# spinner.net
KiCad netlist of a schematic drawn in EAGLE
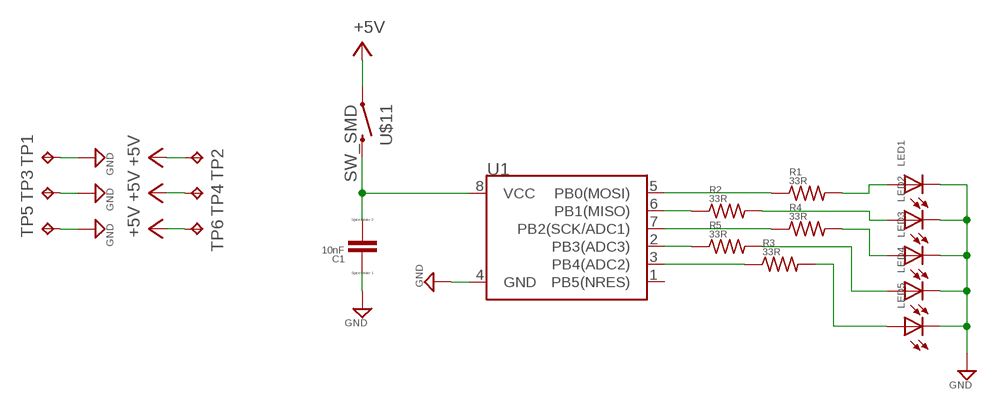
[diagram p0: schematic, sheet 1]

(export (version "E")
  (design (tool "Eeschema 10.0.6"))
  (components
    (comp (ref "C1")
      (value "10nF")
      (footprint "eagle-import:0603")
      (libsource (lib "eagle-import") (part "CAPACITOR-CERAMICOB"))
    )
    (comp (ref "LED1")
      (value "LEDC")
      (footprint "eagle-import:0603LED")
      (libsource (lib "eagle-import") (part "LEDC"))
    )
    (comp (ref "LED2")
      (value "LEDC")
      (footprint "eagle-import:0603LED")
      (libsource (lib "eagle-import") (part "LEDC"))
    )
    (comp (ref "LED3")
      (value "LEDC")
      (footprint "eagle-import:0603LED")
      (libsource (lib "eagle-import") (part "LEDC"))
    )
    (comp (ref "LED4")
      (value "LEDC")
      (footprint "eagle-import:0603LED")
      (libsource (lib "eagle-import") (part "LEDC"))
    )
    (comp (ref "LED5")
      (value "LEDC")
      (footprint "eagle-import:0603LED")
      (libsource (lib "eagle-import") (part "LEDC"))
    )
    (comp (ref "R1")
      (value "33R")
      (footprint "eagle-import:0603")
      (libsource (lib "eagle-import") (part "RESISTORB"))
    )
    (comp (ref "R2")
      (value "33R")
      (footprint "eagle-import:0603")
      (libsource (lib "eagle-import") (part "RESISTORB"))
    )
    (comp (ref "R3")
      (value "33R")
      (footprint "eagle-import:0603")
      (libsource (lib "eagle-import") (part "RESISTORB"))
    )
    (comp (ref "R4")
      (value "33R")
      (footprint "eagle-import:0603")
      (libsource (lib "eagle-import") (part "RESISTORB"))
    )
    (comp (ref "R5")
      (value "33R")
      (footprint "eagle-import:0603")
      (libsource (lib "eagle-import") (part "RESISTORB"))
    )
    (comp (ref "TP1")
      (value "TPB1,27")
      (footprint "eagle-import:B1,27")
      (libsource (lib "eagle-import") (part "TPB1,27"))
    )
    (comp (ref "TP2")
      (value "TPB1,27")
      (footprint "eagle-import:B1,27")
      (libsource (lib "eagle-import") (part "TPB1,27"))
    )
    (comp (ref "TP3")
      (value "TPB1,27")
      (footprint "eagle-import:B1,27")
      (libsource (lib "eagle-import") (part "TPB1,27"))
    )
    (comp (ref "TP4")
      (value "TPB1,27")
      (footprint "eagle-import:B1,27")
      (libsource (lib "eagle-import") (part "TPB1,27"))
    )
    (comp (ref "TP5")
      (value "TPB1,27")
      (footprint "eagle-import:B1,27")
      (libsource (lib "eagle-import") (part "TPB1,27"))
    )
    (comp (ref "TP6")
      (value "TPB1,27")
      (footprint "eagle-import:B1,27")
      (libsource (lib "eagle-import") (part "TPB1,27"))
    )
    (comp (ref "U$11")
      (value "SW_SMD")
      (footprint "eagle-import:SW_SMD")
      (libsource (lib "eagle-import") (part "SW_SMD"))
    )
    (comp (ref "U1")
      (value "Tiny85-20-SMT")
      (footprint "eagle-import:SO08-EIAJ")
      (libsource (lib "eagle-import") (part "ATTINY45"))
    )
  )
  (nets
    (net (code "1") (name "+5V") (class "Default")
      (node (ref "TP2") (pin "TP") (pinfunction "TP_TP") (pintype "input"))
      (node (ref "TP4") (pin "TP") (pinfunction "TP_TP") (pintype "input"))
      (node (ref "TP6") (pin "TP") (pinfunction "TP_TP") (pintype "input"))
      (node (ref "U$11") (pin "1") (pinfunction "1_1") (pintype "passive"))
    )
    (net (code "2") (name "GND") (class "Default")
      (node (ref "C1") (pin "1") (pinfunction "1_1") (pintype "passive"))
      (node (ref "LED1") (pin "K") (pinfunction "C_K") (pintype "passive"))
      (node (ref "LED2") (pin "K") (pinfunction "C_K") (pintype "passive"))
      (node (ref "LED3") (pin "K") (pinfunction "C_K") (pintype "passive"))
      (node (ref "LED4") (pin "K") (pinfunction "C_K") (pintype "passive"))
      (node (ref "LED5") (pin "K") (pinfunction "C_K") (pintype "passive"))
      (node (ref "TP1") (pin "TP") (pinfunction "TP_TP") (pintype "input"))
      (node (ref "TP3") (pin "TP") (pinfunction "TP_TP") (pintype "input"))
      (node (ref "TP5") (pin "TP") (pinfunction "TP_TP") (pintype "input"))
      (node (ref "U1") (pin "4") (pinfunction "GND_4") (pintype "bidirectional"))
    )
    (net (code "3") (name "Net-(LED1-PadA)") (class "Default")
      (node (ref "LED1") (pin "A") (pinfunction "A_A") (pintype "passive"))
      (node (ref "R1") (pin "2") (pinfunction "2_2") (pintype "passive"))
    )
    (net (code "4") (name "Net-(LED2-PadA)") (class "Default")
      (node (ref "LED2") (pin "A") (pinfunction "A_A") (pintype "passive"))
      (node (ref "R2") (pin "2") (pinfunction "2_2") (pintype "passive"))
    )
    (net (code "5") (name "Net-(LED3-PadA)") (class "Default")
      (node (ref "LED3") (pin "A") (pinfunction "A_A") (pintype "passive"))
      (node (ref "R4") (pin "2") (pinfunction "2_2") (pintype "passive"))
    )
    (net (code "6") (name "Net-(LED4-PadA)") (class "Default")
      (node (ref "LED4") (pin "A") (pinfunction "A_A") (pintype "passive"))
      (node (ref "R5") (pin "2") (pinfunction "2_2") (pintype "passive"))
    )
    (net (code "7") (name "Net-(LED5-PadA)") (class "Default")
      (node (ref "LED5") (pin "A") (pinfunction "A_A") (pintype "passive"))
      (node (ref "R3") (pin "2") (pinfunction "2_2") (pintype "passive"))
    )
    (net (code "8") (name "Net-(U1-PB0(MOSI))") (class "Default")
      (node (ref "R1") (pin "1") (pinfunction "1_1") (pintype "passive"))
      (node (ref "U1") (pin "5") (pinfunction "PB0(MOSI)_5") (pintype "bidirectional"))
    )
    (net (code "9") (name "Net-(U1-PB1(MISO))") (class "Default")
      (node (ref "R2") (pin "1") (pinfunction "1_1") (pintype "passive"))
      (node (ref "U1") (pin "6") (pinfunction "PB1(MISO)_6") (pintype "bidirectional"))
    )
    (net (code "10") (name "Net-(U1-PB2(SCK{slash}ADC1))") (class "Default")
      (node (ref "R4") (pin "1") (pinfunction "1_1") (pintype "passive"))
      (node (ref "U1") (pin "7") (pinfunction "PB2(SCK/ADC1)_7") (pintype "bidirectional"))
    )
    (net (code "11") (name "Net-(U1-PB3(ADC3))") (class "Default")
      (node (ref "R5") (pin "1") (pinfunction "1_1") (pintype "passive"))
      (node (ref "U1") (pin "2") (pinfunction "PB3(ADC3)_2") (pintype "bidirectional"))
    )
    (net (code "12") (name "Net-(U1-PB4(ADC2))") (class "Default")
      (node (ref "R3") (pin "1") (pinfunction "1_1") (pintype "passive"))
      (node (ref "U1") (pin "3") (pinfunction "PB4(ADC2)_3") (pintype "bidirectional"))
    )
    (net (code "13") (name "Net-(U1-VCC)") (class "Default")
      (node (ref "C1") (pin "2") (pinfunction "2_2") (pintype "passive"))
      (node (ref "U$11") (pin "2") (pinfunction "2_2") (pintype "passive"))
      (node (ref "U1") (pin "8") (pinfunction "VCC_8") (pintype "bidirectional"))
    )
    (net (code "14") (name "unconnected-(U1-PB5(NRES)-Pad1)") (class "Default")
      (node (ref "U1") (pin "1") (pinfunction "PB5(NRES)_1") (pintype "bidirectional"))
    )
  )
)
